# Zynq_DDR_Interface_Termination.net
KiCad netlist of a schematic drawn in Altium Designer
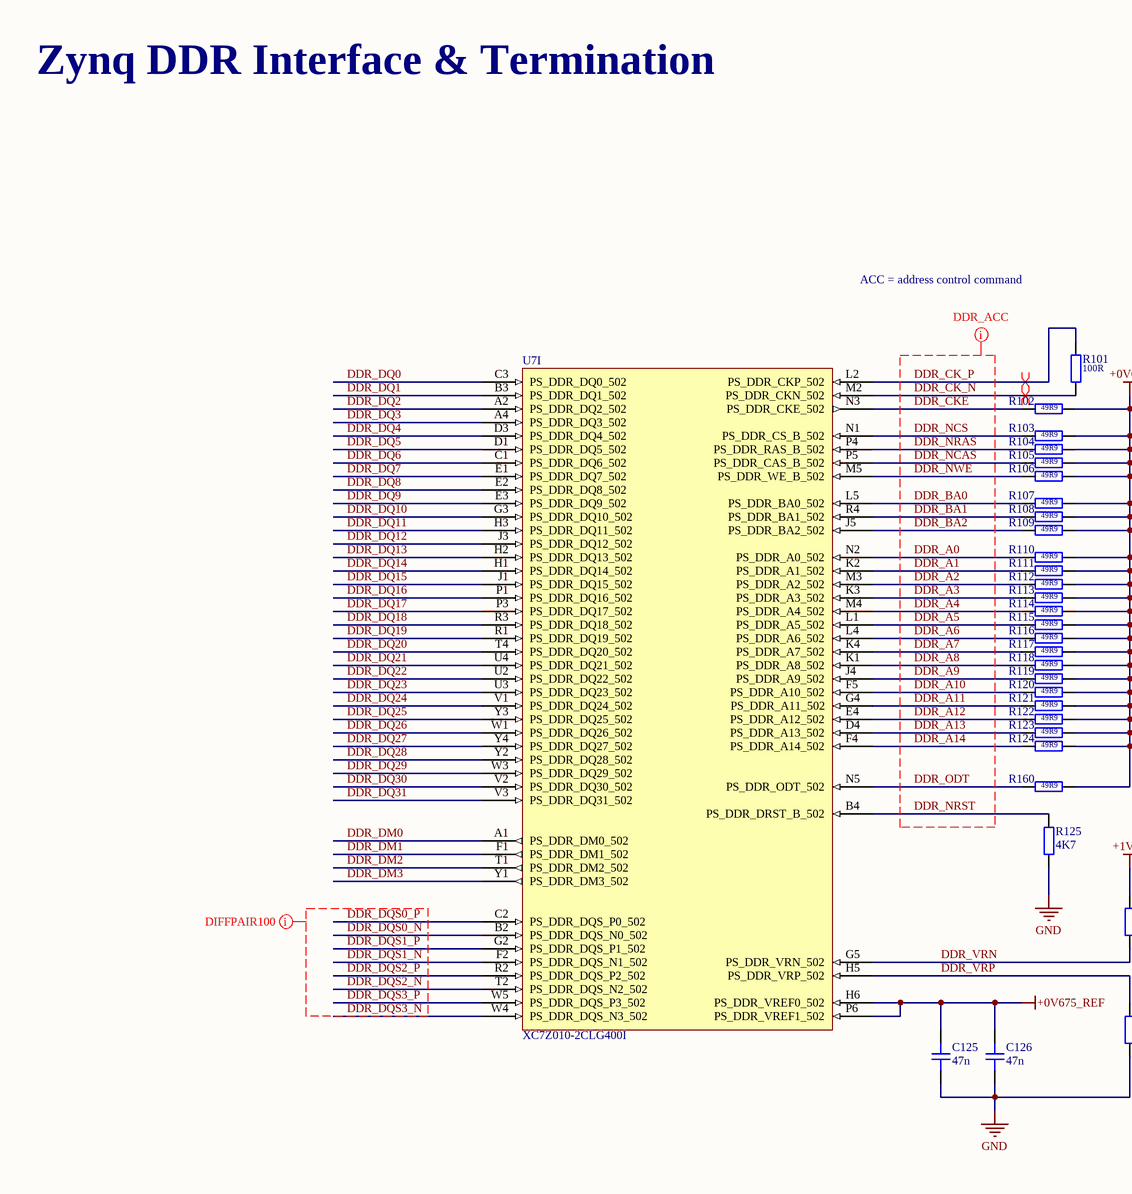
[diagram p0: Zynq DDR Interface & Termination.SchDoc, left]
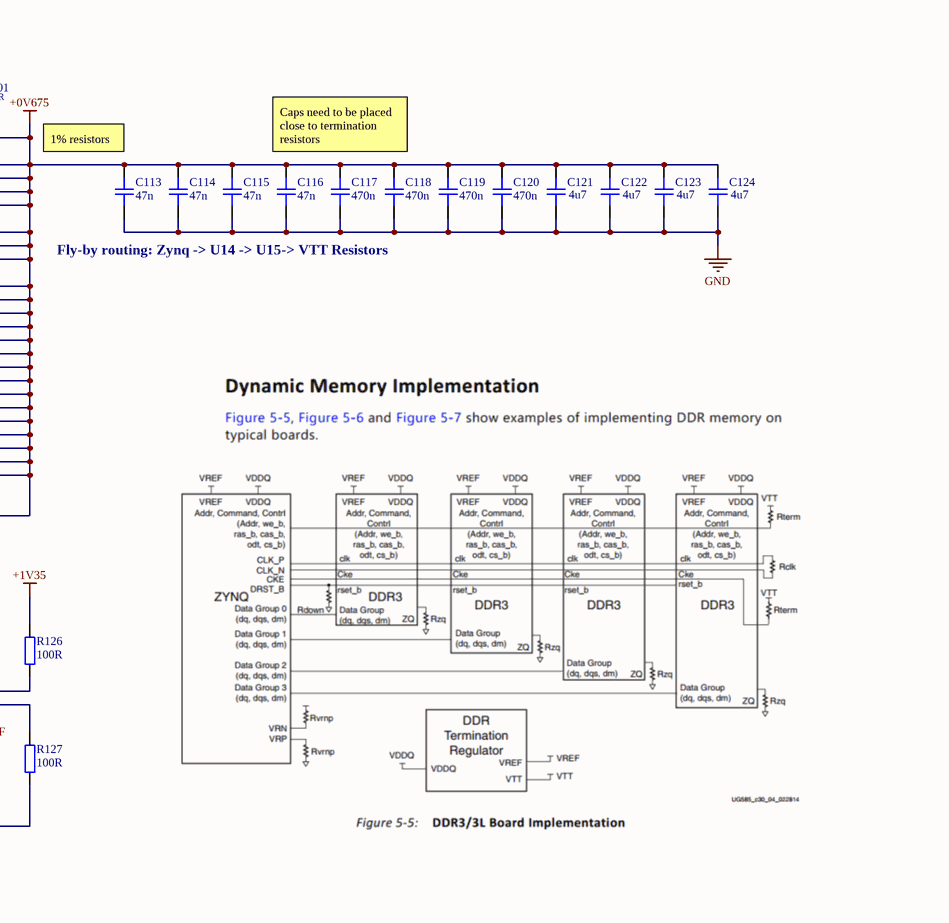
[diagram p1: Zynq DDR Interface & Termination.SchDoc, middle]

(export (version "E")
  (design (tool "Eeschema 10.0.6"))
  (components
    (comp (ref "C113")
      (value "47n")
      (footprint "CAP_0201")
      (description "Capacitor SMD 0201")
      (fields (field (name "Comment") "C0201"))
      (libsource (lib "Schematic-Lib-PhilsLab") (part "CAP_0201"))
    )
    (comp (ref "C114")
      (value "47n")
      (footprint "CAP_0201")
      (description "Capacitor SMD 0201")
      (fields (field (name "Comment") "C0201"))
      (libsource (lib "Schematic-Lib-PhilsLab") (part "CAP_0201"))
    )
    (comp (ref "C115")
      (value "47n")
      (footprint "CAP_0201")
      (description "Capacitor SMD 0201")
      (fields (field (name "Comment") "C0201"))
      (libsource (lib "Schematic-Lib-PhilsLab") (part "CAP_0201"))
    )
    (comp (ref "C116")
      (value "47n")
      (footprint "CAP_0201")
      (description "Capacitor SMD 0201")
      (fields (field (name "Comment") "C0201"))
      (libsource (lib "Schematic-Lib-PhilsLab") (part "CAP_0201"))
    )
    (comp (ref "C117")
      (value "470n")
      (footprint "CAP_0201")
      (description "Capacitor SMD 0201")
      (fields (field (name "Comment") "C0201"))
      (libsource (lib "Schematic-Lib-PhilsLab") (part "CAP_0201"))
    )
    (comp (ref "C118")
      (value "470n")
      (footprint "CAP_0201")
      (description "Capacitor SMD 0201")
      (fields (field (name "Comment") "C0201"))
      (libsource (lib "Schematic-Lib-PhilsLab") (part "CAP_0201"))
    )
    (comp (ref "C119")
      (value "470n")
      (footprint "CAP_0201")
      (description "Capacitor SMD 0201")
      (fields (field (name "Comment") "C0201"))
      (libsource (lib "Schematic-Lib-PhilsLab") (part "CAP_0201"))
    )
    (comp (ref "C120")
      (value "470n")
      (footprint "CAP_0201")
      (description "Capacitor SMD 0201")
      (fields (field (name "Comment") "C0201"))
      (libsource (lib "Schematic-Lib-PhilsLab") (part "CAP_0201"))
    )
    (comp (ref "C121")
      (value "4u7")
      (footprint "CAP_0402")
      (description "Capacitor SMD 0402")
      (fields (field (name "Comment") "C0402"))
      (libsource (lib "Schematic-Lib-PhilsLab") (part "CAP_0402"))
    )
    (comp (ref "C122")
      (value "4u7")
      (footprint "CAP_0402")
      (description "Capacitor SMD 0402")
      (fields (field (name "Comment") "C0402"))
      (libsource (lib "Schematic-Lib-PhilsLab") (part "CAP_0402"))
    )
    (comp (ref "C123")
      (value "4u7")
      (footprint "CAP_0402")
      (description "Capacitor SMD 0402")
      (fields (field (name "Comment") "C0402"))
      (libsource (lib "Schematic-Lib-PhilsLab") (part "CAP_0402"))
    )
    (comp (ref "C124")
      (value "4u7")
      (footprint "CAP_0402")
      (description "Capacitor SMD 0402")
      (fields (field (name "Comment") "C0402"))
      (libsource (lib "Schematic-Lib-PhilsLab") (part "CAP_0402"))
    )
    (comp (ref "C125")
      (value "47n")
      (footprint "CAP_0201")
      (description "Capacitor SMD 0201")
      (fields (field (name "Comment") "C0201"))
      (libsource (lib "Schematic-Lib-PhilsLab") (part "CAP_0201"))
    )
    (comp (ref "C126")
      (value "47n")
      (footprint "CAP_0201")
      (description "Capacitor SMD 0201")
      (fields (field (name "Comment") "C0201"))
      (libsource (lib "Schematic-Lib-PhilsLab") (part "CAP_0201"))
    )
    (comp (ref "R101")
      (value "100R")
      (footprint "RES_0201")
      (description "Resistor SMD 0201")
      (fields (field (name "Comment") "R0201"))
      (libsource (lib "Schematic-Lib-PhilsLab") (part "RES_0201"))
    )
    (comp (ref "R102")
      (value "49R9")
      (footprint "RES_0201")
      (description "Resistor SMD 0201")
      (fields (field (name "Comment") "R0201"))
      (libsource (lib "Schematic-Lib-PhilsLab") (part "RES_0201"))
    )
    (comp (ref "R103")
      (value "49R9")
      (footprint "RES_0201")
      (description "Resistor SMD 0201")
      (fields (field (name "Comment") "R0201"))
      (libsource (lib "Schematic-Lib-PhilsLab") (part "RES_0201"))
    )
    (comp (ref "R104")
      (value "49R9")
      (footprint "RES_0201")
      (description "Resistor SMD 0201")
      (fields (field (name "Comment") "R0201"))
      (libsource (lib "Schematic-Lib-PhilsLab") (part "RES_0201"))
    )
    (comp (ref "R105")
      (value "49R9")
      (footprint "RES_0201")
      (description "Resistor SMD 0201")
      (fields (field (name "Comment") "R0201"))
      (libsource (lib "Schematic-Lib-PhilsLab") (part "RES_0201"))
    )
    (comp (ref "R106")
      (value "49R9")
      (footprint "RES_0201")
      (description "Resistor SMD 0201")
      (fields (field (name "Comment") "R0201"))
      (libsource (lib "Schematic-Lib-PhilsLab") (part "RES_0201"))
    )
    (comp (ref "R107")
      (value "49R9")
      (footprint "RES_0201")
      (description "Resistor SMD 0201")
      (fields (field (name "Comment") "R0201"))
      (libsource (lib "Schematic-Lib-PhilsLab") (part "RES_0201"))
    )
    (comp (ref "R108")
      (value "49R9")
      (footprint "RES_0201")
      (description "Resistor SMD 0201")
      (fields (field (name "Comment") "R0201"))
      (libsource (lib "Schematic-Lib-PhilsLab") (part "RES_0201"))
    )
    (comp (ref "R109")
      (value "49R9")
      (footprint "RES_0201")
      (description "Resistor SMD 0201")
      (fields (field (name "Comment") "R0201"))
      (libsource (lib "Schematic-Lib-PhilsLab") (part "RES_0201"))
    )
    (comp (ref "R110")
      (value "49R9")
      (footprint "RES_0201")
      (description "Resistor SMD 0201")
      (fields (field (name "Comment") "R0201"))
      (libsource (lib "Schematic-Lib-PhilsLab") (part "RES_0201"))
    )
    (comp (ref "R111")
      (value "49R9")
      (footprint "RES_0201")
      (description "Resistor SMD 0201")
      (fields (field (name "Comment") "R0201"))
      (libsource (lib "Schematic-Lib-PhilsLab") (part "RES_0201"))
    )
    (comp (ref "R112")
      (value "49R9")
      (footprint "RES_0201")
      (description "Resistor SMD 0201")
      (fields (field (name "Comment") "R0201"))
      (libsource (lib "Schematic-Lib-PhilsLab") (part "RES_0201"))
    )
    (comp (ref "R113")
      (value "49R9")
      (footprint "RES_0201")
      (description "Resistor SMD 0201")
      (fields (field (name "Comment") "R0201"))
      (libsource (lib "Schematic-Lib-PhilsLab") (part "RES_0201"))
    )
    (comp (ref "R114")
      (value "49R9")
      (footprint "RES_0201")
      (description "Resistor SMD 0201")
      (fields (field (name "Comment") "R0201"))
      (libsource (lib "Schematic-Lib-PhilsLab") (part "RES_0201"))
    )
    (comp (ref "R115")
      (value "49R9")
      (footprint "RES_0201")
      (description "Resistor SMD 0201")
      (fields (field (name "Comment") "R0201"))
      (libsource (lib "Schematic-Lib-PhilsLab") (part "RES_0201"))
    )
    (comp (ref "R116")
      (value "49R9")
      (footprint "RES_0201")
      (description "Resistor SMD 0201")
      (fields (field (name "Comment") "R0201"))
      (libsource (lib "Schematic-Lib-PhilsLab") (part "RES_0201"))
    )
    (comp (ref "R117")
      (value "49R9")
      (footprint "RES_0201")
      (description "Resistor SMD 0201")
      (fields (field (name "Comment") "R0201"))
      (libsource (lib "Schematic-Lib-PhilsLab") (part "RES_0201"))
    )
    (comp (ref "R118")
      (value "49R9")
      (footprint "RES_0201")
      (description "Resistor SMD 0201")
      (fields (field (name "Comment") "R0201"))
      (libsource (lib "Schematic-Lib-PhilsLab") (part "RES_0201"))
    )
    (comp (ref "R119")
      (value "49R9")
      (footprint "RES_0201")
      (description "Resistor SMD 0201")
      (fields (field (name "Comment") "R0201"))
      (libsource (lib "Schematic-Lib-PhilsLab") (part "RES_0201"))
    )
    (comp (ref "R120")
      (value "49R9")
      (footprint "RES_0201")
      (description "Resistor SMD 0201")
      (fields (field (name "Comment") "R0201"))
      (libsource (lib "Schematic-Lib-PhilsLab") (part "RES_0201"))
    )
    (comp (ref "R121")
      (value "49R9")
      (footprint "RES_0201")
      (description "Resistor SMD 0201")
      (fields (field (name "Comment") "R0201"))
      (libsource (lib "Schematic-Lib-PhilsLab") (part "RES_0201"))
    )
    (comp (ref "R122")
      (value "49R9")
      (footprint "RES_0201")
      (description "Resistor SMD 0201")
      (fields (field (name "Comment") "R0201"))
      (libsource (lib "Schematic-Lib-PhilsLab") (part "RES_0201"))
    )
    (comp (ref "R123")
      (value "49R9")
      (footprint "RES_0201")
      (description "Resistor SMD 0201")
      (fields (field (name "Comment") "R0201"))
      (libsource (lib "Schematic-Lib-PhilsLab") (part "RES_0201"))
    )
    (comp (ref "R124")
      (value "49R9")
      (footprint "RES_0201")
      (description "Resistor SMD 0201")
      (fields (field (name "Comment") "R0201"))
      (libsource (lib "Schematic-Lib-PhilsLab") (part "RES_0201"))
    )
    (comp (ref "R125")
      (value "4K7")
      (footprint "RES_0402")
      (description "Resistor SMD 0402")
      (fields (field (name "Comment") "R0402"))
      (libsource (lib "Schematic-Lib-PhilsLab") (part "RES_0402"))
    )
    (comp (ref "R126")
      (value "100R")
      (footprint "RES_0402")
      (description "Resistor SMD 0402")
      (fields (field (name "Comment") "R0402"))
      (libsource (lib "Schematic-Lib-PhilsLab") (part "RES_0402"))
    )
    (comp (ref "R127")
      (value "100R")
      (footprint "RES_0402")
      (description "Resistor SMD 0402")
      (fields (field (name "Comment") "R0402"))
      (libsource (lib "Schematic-Lib-PhilsLab") (part "RES_0402"))
    )
    (comp (ref "R160")
      (value "49R9")
      (footprint "RES_0201")
      (description "Resistor SMD 0201")
      (fields (field (name "Comment") "R0201"))
      (libsource (lib "Schematic-Lib-PhilsLab") (part "RES_0201"))
    )
    (comp (ref "U7")
      (value "XC7Z010-2CLG400I")
      (footprint "BGA400C80P20X20_1700X1700X160N")
      (libsource (lib "Zynq_SOM") (part "XC7Z010-2CLG400I"))
    )
  )
  (nets
    (net (code "1") (name "+0V675") (class "Default")
      (node (ref "C113") (pin "2") (pinfunction "2_2") (pintype "passive"))
      (node (ref "C114") (pin "2") (pinfunction "2_2") (pintype "passive"))
      (node (ref "C115") (pin "2") (pinfunction "2_2") (pintype "passive"))
      (node (ref "C116") (pin "2") (pinfunction "2_2") (pintype "passive"))
      (node (ref "C117") (pin "2") (pinfunction "2_2") (pintype "passive"))
      (node (ref "C118") (pin "2") (pinfunction "2_2") (pintype "passive"))
      (node (ref "C119") (pin "2") (pinfunction "2_2") (pintype "passive"))
      (node (ref "C120") (pin "2") (pinfunction "2_2") (pintype "passive"))
      (node (ref "C121") (pin "2") (pinfunction "2_2") (pintype "passive"))
      (node (ref "C122") (pin "2") (pinfunction "2_2") (pintype "passive"))
      (node (ref "C123") (pin "2") (pinfunction "2_2") (pintype "passive"))
      (node (ref "C124") (pin "2") (pinfunction "2_2") (pintype "passive"))
      (node (ref "R102") (pin "2") (pinfunction "2_2") (pintype "passive"))
      (node (ref "R103") (pin "2") (pinfunction "2_2") (pintype "passive"))
      (node (ref "R104") (pin "2") (pinfunction "2_2") (pintype "passive"))
      (node (ref "R105") (pin "2") (pinfunction "2_2") (pintype "passive"))
      (node (ref "R106") (pin "2") (pinfunction "2_2") (pintype "passive"))
      (node (ref "R107") (pin "2") (pinfunction "2_2") (pintype "passive"))
      (node (ref "R108") (pin "2") (pinfunction "2_2") (pintype "passive"))
      (node (ref "R109") (pin "2") (pinfunction "2_2") (pintype "passive"))
      (node (ref "R110") (pin "2") (pinfunction "2_2") (pintype "passive"))
      (node (ref "R111") (pin "2") (pinfunction "2_2") (pintype "passive"))
      (node (ref "R112") (pin "2") (pinfunction "2_2") (pintype "passive"))
      (node (ref "R113") (pin "2") (pinfunction "2_2") (pintype "passive"))
      (node (ref "R114") (pin "2") (pinfunction "2_2") (pintype "passive"))
      (node (ref "R115") (pin "2") (pinfunction "2_2") (pintype "passive"))
      (node (ref "R116") (pin "2") (pinfunction "2_2") (pintype "passive"))
      (node (ref "R117") (pin "2") (pinfunction "2_2") (pintype "passive"))
      (node (ref "R118") (pin "2") (pinfunction "2_2") (pintype "passive"))
      (node (ref "R119") (pin "2") (pinfunction "2_2") (pintype "passive"))
      (node (ref "R120") (pin "2") (pinfunction "2_2") (pintype "passive"))
      (node (ref "R121") (pin "2") (pinfunction "2_2") (pintype "passive"))
      (node (ref "R122") (pin "2") (pinfunction "2_2") (pintype "passive"))
      (node (ref "R123") (pin "2") (pinfunction "2_2") (pintype "passive"))
      (node (ref "R124") (pin "2") (pinfunction "2_2") (pintype "passive"))
      (node (ref "R160") (pin "2") (pinfunction "2_2") (pintype "passive"))
    )
    (net (code "2") (name "+0V675_REF") (class "Default")
      (node (ref "C125") (pin "2") (pinfunction "2_2") (pintype "passive"))
      (node (ref "C126") (pin "2") (pinfunction "2_2") (pintype "passive"))
      (node (ref "U7") (pin "H6") (pinfunction "PS_DDR_VREF0_502_H6") (pintype "input"))
      (node (ref "U7") (pin "P6") (pinfunction "PS_DDR_VREF1_502_P6") (pintype "input"))
    )
    (net (code "3") (name "+1V35") (class "Default")
      (node (ref "R126") (pin "1") (pinfunction "1_1") (pintype "passive"))
    )
    (net (code "4") (name "/DDR_A0") (class "Default")
      (node (ref "R110") (pin "1") (pinfunction "1_1") (pintype "passive"))
      (node (ref "U7") (pin "N2") (pinfunction "PS_DDR_A0_502_N2") (pintype "input"))
    )
    (net (code "5") (name "/DDR_A1") (class "Default")
      (node (ref "R111") (pin "1") (pinfunction "1_1") (pintype "passive"))
      (node (ref "U7") (pin "K2") (pinfunction "PS_DDR_A1_502_K2") (pintype "input"))
    )
    (net (code "6") (name "/DDR_A2") (class "Default")
      (node (ref "R112") (pin "1") (pinfunction "1_1") (pintype "passive"))
      (node (ref "U7") (pin "M3") (pinfunction "PS_DDR_A2_502_M3") (pintype "input"))
    )
    (net (code "7") (name "/DDR_A3") (class "Default")
      (node (ref "R113") (pin "1") (pinfunction "1_1") (pintype "passive"))
      (node (ref "U7") (pin "K3") (pinfunction "PS_DDR_A3_502_K3") (pintype "input"))
    )
    (net (code "8") (name "/DDR_A4") (class "Default")
      (node (ref "R114") (pin "1") (pinfunction "1_1") (pintype "passive"))
      (node (ref "U7") (pin "M4") (pinfunction "PS_DDR_A4_502_M4") (pintype "input"))
    )
    (net (code "9") (name "/DDR_A5") (class "Default")
      (node (ref "R115") (pin "1") (pinfunction "1_1") (pintype "passive"))
      (node (ref "U7") (pin "L1") (pinfunction "PS_DDR_A5_502_L1") (pintype "input"))
    )
    (net (code "10") (name "/DDR_A6") (class "Default")
      (node (ref "R116") (pin "1") (pinfunction "1_1") (pintype "passive"))
      (node (ref "U7") (pin "L4") (pinfunction "PS_DDR_A6_502_L4") (pintype "input"))
    )
    (net (code "11") (name "/DDR_A7") (class "Default")
      (node (ref "R117") (pin "1") (pinfunction "1_1") (pintype "passive"))
      (node (ref "U7") (pin "K4") (pinfunction "PS_DDR_A7_502_K4") (pintype "input"))
    )
    (net (code "12") (name "/DDR_A8") (class "Default")
      (node (ref "R118") (pin "1") (pinfunction "1_1") (pintype "passive"))
      (node (ref "U7") (pin "K1") (pinfunction "PS_DDR_A8_502_K1") (pintype "input"))
    )
    (net (code "13") (name "/DDR_A9") (class "Default")
      (node (ref "R119") (pin "1") (pinfunction "1_1") (pintype "passive"))
      (node (ref "U7") (pin "J4") (pinfunction "PS_DDR_A9_502_J4") (pintype "input"))
    )
    (net (code "14") (name "/DDR_A10") (class "Default")
      (node (ref "R120") (pin "1") (pinfunction "1_1") (pintype "passive"))
      (node (ref "U7") (pin "F5") (pinfunction "PS_DDR_A10_502_F5") (pintype "input"))
    )
    (net (code "15") (name "/DDR_A11") (class "Default")
      (node (ref "R121") (pin "1") (pinfunction "1_1") (pintype "passive"))
      (node (ref "U7") (pin "G4") (pinfunction "PS_DDR_A11_502_G4") (pintype "input"))
    )
    (net (code "16") (name "/DDR_A12") (class "Default")
      (node (ref "R122") (pin "1") (pinfunction "1_1") (pintype "passive"))
      (node (ref "U7") (pin "E4") (pinfunction "PS_DDR_A12_502_E4") (pintype "input"))
    )
    (net (code "17") (name "/DDR_A13") (class "Default")
      (node (ref "R123") (pin "1") (pinfunction "1_1") (pintype "passive"))
      (node (ref "U7") (pin "D4") (pinfunction "PS_DDR_A13_502_D4") (pintype "input"))
    )
    (net (code "18") (name "/DDR_A14") (class "Default")
      (node (ref "R124") (pin "1") (pinfunction "1_1") (pintype "passive"))
      (node (ref "U7") (pin "F4") (pinfunction "PS_DDR_A14_502_F4") (pintype "input"))
    )
    (net (code "19") (name "/DDR_BA0") (class "Default")
      (node (ref "R107") (pin "1") (pinfunction "1_1") (pintype "passive"))
      (node (ref "U7") (pin "L5") (pinfunction "PS_DDR_BA0_502_L5") (pintype "input"))
    )
    (net (code "20") (name "/DDR_BA1") (class "Default")
      (node (ref "R108") (pin "1") (pinfunction "1_1") (pintype "passive"))
      (node (ref "U7") (pin "R4") (pinfunction "PS_DDR_BA1_502_R4") (pintype "input"))
    )
    (net (code "21") (name "/DDR_BA2") (class "Default")
      (node (ref "R109") (pin "1") (pinfunction "1_1") (pintype "passive"))
      (node (ref "U7") (pin "J5") (pinfunction "PS_DDR_BA2_502_J5") (pintype "input"))
    )
    (net (code "22") (name "/DDR_CKE") (class "Default")
      (node (ref "R102") (pin "1") (pinfunction "1_1") (pintype "passive"))
      (node (ref "U7") (pin "N3") (pinfunction "PS_DDR_CKE_502_N3") (pintype "output"))
    )
    (net (code "23") (name "/DDR_CK_N") (class "Default")
      (node (ref "R101") (pin "1") (pinfunction "1_1") (pintype "passive"))
      (node (ref "U7") (pin "M2") (pinfunction "PS_DDR_CKN_502_M2") (pintype "input"))
    )
    (net (code "24") (name "/DDR_CK_P") (class "Default")
      (node (ref "R101") (pin "2") (pinfunction "2_2") (pintype "passive"))
      (node (ref "U7") (pin "L2") (pinfunction "PS_DDR_CKP_502_L2") (pintype "input"))
    )
    (net (code "25") (name "/DDR_DM0") (class "Default")
      (node (ref "U7") (pin "A1") (pinfunction "PS_DDR_DM0_502_A1") (pintype "output"))
    )
    (net (code "26") (name "/DDR_DM1") (class "Default")
      (node (ref "U7") (pin "F1") (pinfunction "PS_DDR_DM1_502_F1") (pintype "output"))
    )
    (net (code "27") (name "/DDR_DM2") (class "Default")
      (node (ref "U7") (pin "T1") (pinfunction "PS_DDR_DM2_502_T1") (pintype "output"))
    )
    (net (code "28") (name "/DDR_DM3") (class "Default")
      (node (ref "U7") (pin "Y1") (pinfunction "PS_DDR_DM3_502_Y1") (pintype "output"))
    )
    (net (code "29") (name "/DDR_DQ0") (class "Default")
      (node (ref "U7") (pin "C3") (pinfunction "PS_DDR_DQ0_502_C3") (pintype "input"))
    )
    (net (code "30") (name "/DDR_DQ1") (class "Default")
      (node (ref "U7") (pin "B3") (pinfunction "PS_DDR_DQ1_502_B3") (pintype "input"))
    )
    (net (code "31") (name "/DDR_DQ2") (class "Default")
      (node (ref "U7") (pin "A2") (pinfunction "PS_DDR_DQ2_502_A2") (pintype "input"))
    )
    (net (code "32") (name "/DDR_DQ3") (class "Default")
      (node (ref "U7") (pin "A4") (pinfunction "PS_DDR_DQ3_502_A4") (pintype "input"))
    )
    (net (code "33") (name "/DDR_DQ4") (class "Default")
      (node (ref "U7") (pin "D3") (pinfunction "PS_DDR_DQ4_502_D3") (pintype "input"))
    )
    (net (code "34") (name "/DDR_DQ5") (class "Default")
      (node (ref "U7") (pin "D1") (pinfunction "PS_DDR_DQ5_502_D1") (pintype "input"))
    )
    (net (code "35") (name "/DDR_DQ6") (class "Default")
      (node (ref "U7") (pin "C1") (pinfunction "PS_DDR_DQ6_502_C1") (pintype "input"))
    )
    (net (code "36") (name "/DDR_DQ7") (class "Default")
      (node (ref "U7") (pin "E1") (pinfunction "PS_DDR_DQ7_502_E1") (pintype "input"))
    )
    (net (code "37") (name "/DDR_DQ8") (class "Default")
      (node (ref "U7") (pin "E2") (pinfunction "PS_DDR_DQ8_502_E2") (pintype "input"))
    )
    (net (code "38") (name "/DDR_DQ9") (class "Default")
      (node (ref "U7") (pin "E3") (pinfunction "PS_DDR_DQ9_502_E3") (pintype "input"))
    )
    (net (code "39") (name "/DDR_DQ10") (class "Default")
      (node (ref "U7") (pin "G3") (pinfunction "PS_DDR_DQ10_502_G3") (pintype "input"))
    )
    (net (code "40") (name "/DDR_DQ11") (class "Default")
      (node (ref "U7") (pin "H3") (pinfunction "PS_DDR_DQ11_502_H3") (pintype "input"))
    )
    (net (code "41") (name "/DDR_DQ12") (class "Default")
      (node (ref "U7") (pin "J3") (pinfunction "PS_DDR_DQ12_502_J3") (pintype "input"))
    )
    (net (code "42") (name "/DDR_DQ13") (class "Default")
      (node (ref "U7") (pin "H2") (pinfunction "PS_DDR_DQ13_502_H2") (pintype "input"))
    )
    (net (code "43") (name "/DDR_DQ14") (class "Default")
      (node (ref "U7") (pin "H1") (pinfunction "PS_DDR_DQ14_502_H1") (pintype "input"))
    )
    (net (code "44") (name "/DDR_DQ15") (class "Default")
      (node (ref "U7") (pin "J1") (pinfunction "PS_DDR_DQ15_502_J1") (pintype "input"))
    )
    (net (code "45") (name "/DDR_DQ16") (class "Default")
      (node (ref "U7") (pin "P1") (pinfunction "PS_DDR_DQ16_502_P1") (pintype "input"))
    )
    (net (code "46") (name "/DDR_DQ17") (class "Default")
      (node (ref "U7") (pin "P3") (pinfunction "PS_DDR_DQ17_502_P3") (pintype "input"))
    )
    (net (code "47") (name "/DDR_DQ18") (class "Default")
      (node (ref "U7") (pin "R3") (pinfunction "PS_DDR_DQ18_502_R3") (pintype "input"))
    )
    (net (code "48") (name "/DDR_DQ19") (class "Default")
      (node (ref "U7") (pin "R1") (pinfunction "PS_DDR_DQ19_502_R1") (pintype "input"))
    )
    (net (code "49") (name "/DDR_DQ20") (class "Default")
      (node (ref "U7") (pin "T4") (pinfunction "PS_DDR_DQ20_502_T4") (pintype "input"))
    )
    (net (code "50") (name "/DDR_DQ21") (class "Default")
      (node (ref "U7") (pin "U4") (pinfunction "PS_DDR_DQ21_502_U4") (pintype "input"))
    )
    (net (code "51") (name "/DDR_DQ22") (class "Default")
      (node (ref "U7") (pin "U2") (pinfunction "PS_DDR_DQ22_502_U2") (pintype "input"))
    )
    (net (code "52") (name "/DDR_DQ23") (class "Default")
      (node (ref "U7") (pin "U3") (pinfunction "PS_DDR_DQ23_502_U3") (pintype "input"))
    )
    (net (code "53") (name "/DDR_DQ24") (class "Default")
      (node (ref "U7") (pin "V1") (pinfunction "PS_DDR_DQ24_502_V1") (pintype "input"))
    )
    (net (code "54") (name "/DDR_DQ25") (class "Default")
      (node (ref "U7") (pin "Y3") (pinfunction "PS_DDR_DQ25_502_Y3") (pintype "input"))
    )
    (net (code "55") (name "/DDR_DQ26") (class "Default")
      (node (ref "U7") (pin "W1") (pinfunction "PS_DDR_DQ26_502_W1") (pintype "input"))
    )
    (net (code "56") (name "/DDR_DQ27") (class "Default")
      (node (ref "U7") (pin "Y4") (pinfunction "PS_DDR_DQ27_502_Y4") (pintype "input"))
    )
    (net (code "57") (name "/DDR_DQ28") (class "Default")
      (node (ref "U7") (pin "Y2") (pinfunction "PS_DDR_DQ28_502_Y2") (pintype "input"))
    )
    (net (code "58") (name "/DDR_DQ29") (class "Default")
      (node (ref "U7") (pin "W3") (pinfunction "PS_DDR_DQ29_502_W3") (pintype "input"))
    )
    (net (code "59") (name "/DDR_DQ30") (class "Default")
      (node (ref "U7") (pin "V2") (pinfunction "PS_DDR_DQ30_502_V2") (pintype "input"))
    )
    (net (code "60") (name "/DDR_DQ31") (class "Default")
      (node (ref "U7") (pin "V3") (pinfunction "PS_DDR_DQ31_502_V3") (pintype "input"))
    )
    (net (code "61") (name "/DDR_DQS0_N") (class "Default")
      (node (ref "U7") (pin "B2") (pinfunction "PS_DDR_DQS_N0_502_B2") (pintype "input"))
    )
    (net (code "62") (name "/DDR_DQS0_P") (class "Default")
      (node (ref "U7") (pin "C2") (pinfunction "PS_DDR_DQS_P0_502_C2") (pintype "input"))
    )
    (net (code "63") (name "/DDR_DQS1_N") (class "Default")
      (node (ref "U7") (pin "F2") (pinfunction "PS_DDR_DQS_N1_502_F2") (pintype "input"))
    )
    (net (code "64") (name "/DDR_DQS1_P") (class "Default")
      (node (ref "U7") (pin "G2") (pinfunction "PS_DDR_DQS_P1_502_G2") (pintype "input"))
    )
    (net (code "65") (name "/DDR_DQS2_N") (class "Default")
      (node (ref "U7") (pin "T2") (pinfunction "PS_DDR_DQS_N2_502_T2") (pintype "input"))
    )
    (net (code "66") (name "/DDR_DQS2_P") (class "Default")
      (node (ref "U7") (pin "R2") (pinfunction "PS_DDR_DQS_P2_502_R2") (pintype "input"))
    )
    (net (code "67") (name "/DDR_DQS3_N") (class "Default")
      (node (ref "U7") (pin "W4") (pinfunction "PS_DDR_DQS_N3_502_W4") (pintype "input"))
    )
    (net (code "68") (name "/DDR_DQS3_P") (class "Default")
      (node (ref "U7") (pin "W5") (pinfunction "PS_DDR_DQS_P3_502_W5") (pintype "input"))
    )
    (net (code "69") (name "/DDR_NCAS") (class "Default")
      (node (ref "R105") (pin "1") (pinfunction "1_1") (pintype "passive"))
      (node (ref "U7") (pin "P5") (pinfunction "PS_DDR_CAS_B_502_P5") (pintype "input"))
    )
    (net (code "70") (name "/DDR_NCS") (class "Default")
      (node (ref "R103") (pin "1") (pinfunction "1_1") (pintype "passive"))
      (node (ref "U7") (pin "N1") (pinfunction "PS_DDR_CS_B_502_N1") (pintype "input"))
    )
    (net (code "71") (name "/DDR_NRAS") (class "Default")
      (node (ref "R104") (pin "1") (pinfunction "1_1") (pintype "passive"))
      (node (ref "U7") (pin "P4") (pinfunction "PS_DDR_RAS_B_502_P4") (pintype "input"))
    )
    (net (code "72") (name "/DDR_NRST") (class "Default")
      (node (ref "R125") (pin "1") (pinfunction "1_1") (pintype "passive"))
      (node (ref "U7") (pin "B4") (pinfunction "PS_DDR_DRST_B_502_B4") (pintype "input"))
    )
    (net (code "73") (name "/DDR_NWE") (class "Default")
      (node (ref "R106") (pin "1") (pinfunction "1_1") (pintype "passive"))
      (node (ref "U7") (pin "M5") (pinfunction "PS_DDR_WE_B_502_M5") (pintype "input"))
    )
    (net (code "74") (name "/DDR_ODT") (class "Default")
      (node (ref "R160") (pin "1") (pinfunction "1_1") (pintype "passive"))
      (node (ref "U7") (pin "N5") (pinfunction "PS_DDR_ODT_502_N5") (pintype "input"))
    )
    (net (code "75") (name "/DDR_VRN") (class "Default")
      (node (ref "R126") (pin "2") (pinfunction "2_2") (pintype "passive"))
      (node (ref "U7") (pin "G5") (pinfunction "PS_DDR_VRN_502_G5") (pintype "input"))
    )
    (net (code "76") (name "/DDR_VRP") (class "Default")
      (node (ref "R127") (pin "1") (pinfunction "1_1") (pintype "passive"))
      (node (ref "U7") (pin "H5") (pinfunction "PS_DDR_VRP_502_H5") (pintype "input"))
    )
    (net (code "77") (name "GND") (class "Default")
      (node (ref "C113") (pin "1") (pinfunction "1_1") (pintype "passive"))
      (node (ref "C114") (pin "1") (pinfunction "1_1") (pintype "passive"))
      (node (ref "C115") (pin "1") (pinfunction "1_1") (pintype "passive"))
      (node (ref "C116") (pin "1") (pinfunction "1_1") (pintype "passive"))
      (node (ref "C117") (pin "1") (pinfunction "1_1") (pintype "passive"))
      (node (ref "C118") (pin "1") (pinfunction "1_1") (pintype "passive"))
      (node (ref "C119") (pin "1") (pinfunction "1_1") (pintype "passive"))
      (node (ref "C120") (pin "1") (pinfunction "1_1") (pintype "passive"))
      (node (ref "C121") (pin "1") (pinfunction "1_1") (pintype "passive"))
      (node (ref "C122") (pin "1") (pinfunction "1_1") (pintype "passive"))
      (node (ref "C123") (pin "1") (pinfunction "1_1") (pintype "passive"))
      (node (ref "C124") (pin "1") (pinfunction "1_1") (pintype "passive"))
      (node (ref "C125") (pin "1") (pinfunction "1_1") (pintype "passive"))
      (node (ref "C126") (pin "1") (pinfunction "1_1") (pintype "passive"))
      (node (ref "R125") (pin "2") (pinfunction "2_2") (pintype "passive"))
      (node (ref "R127") (pin "2") (pinfunction "2_2") (pintype "passive"))
    )
  )
)
